# schematic.net
KiCad netlist of a schematic drawn in EAGLE
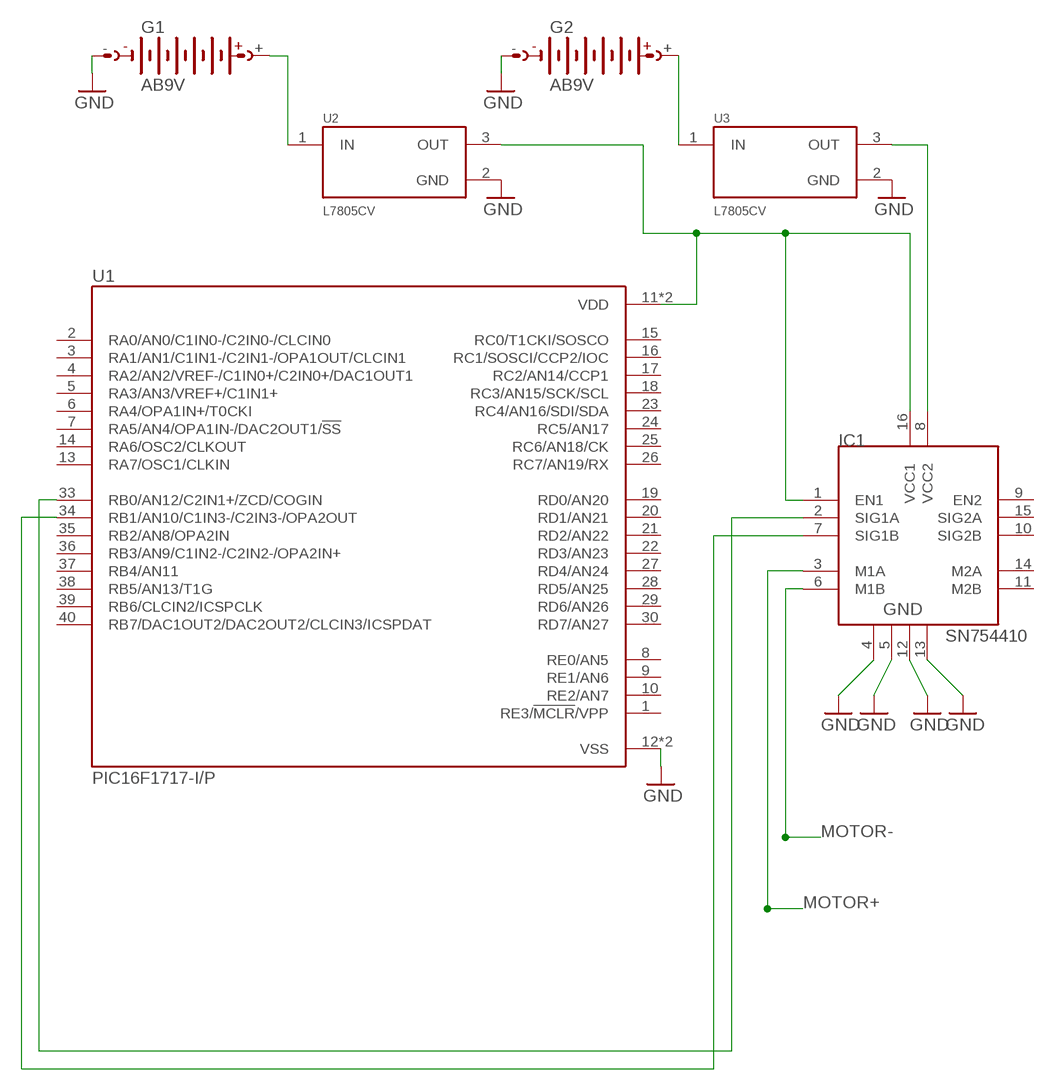
[diagram p0: schematic, sheet 1]

(export (version "E")
  (design (tool "Eeschema 10.0.6"))
  (components
    (comp (ref "G1")
      (value "AB9V")
      (footprint "eagle-import:AB9V")
      (libsource (lib "eagle-import") (part "AB9V"))
    )
    (comp (ref "G2")
      (value "AB9V")
      (footprint "eagle-import:AB9V")
      (libsource (lib "eagle-import") (part "AB9V"))
    )
    (comp (ref "IC1")
      (value "SN754410")
      (footprint "eagle-import:DIP16")
      (libsource (lib "eagle-import") (part "SN754410"))
    )
    (comp (ref "U1")
      (value "PIC16F1717-I/P")
      (footprint "eagle-import:DIP1543W47P254L5321H635Q40")
      (fields (field (name "MF") "Microchip"))
      (libsource (lib "eagle-import") (part "PIC16F1717-I/P"))
    )
    (comp (ref "U2")
      (value "L7805CV")
      (footprint "eagle-import:TO254P460X1020X1945-3P")
      (fields (field (name "MF") "STMicroelectronics"))
      (libsource (lib "eagle-import") (part "L7805CV"))
    )
    (comp (ref "U3")
      (value "L7805CV")
      (footprint "eagle-import:TO254P460X1020X1945-3P")
      (fields (field (name "MF") "STMicroelectronics"))
      (libsource (lib "eagle-import") (part "L7805CV"))
    )
  )
  (nets
    (net (code "1") (name "/MOTOR+") (class "Default")
      (node (ref "IC1") (pin "3") (pinfunction "M1A_3") (pintype "bidirectional"))
    )
    (net (code "2") (name "/MOTOR-") (class "Default")
      (node (ref "IC1") (pin "6") (pinfunction "M1B_6") (pintype "bidirectional"))
    )
    (net (code "3") (name "GND") (class "Default")
      (node (ref "G1") (pin "-") (pinfunction "-_-") (pintype "passive"))
      (node (ref "G2") (pin "-") (pinfunction "-_-") (pintype "passive"))
      (node (ref "IC1") (pin "12") (pinfunction "P12_12") (pintype "power_in"))
      (node (ref "IC1") (pin "13") (pinfunction "P13_13") (pintype "power_in"))
      (node (ref "IC1") (pin "4") (pinfunction "P4_4") (pintype "power_in"))
      (node (ref "IC1") (pin "5") (pinfunction "P5_5") (pintype "power_in"))
      (node (ref "U1") (pin "12") (pinfunction "VSS_12") (pintype "power_in"))
      (node (ref "U1") (pin "31") (pinfunction "VSS_31") (pintype "power_in"))
      (node (ref "U2") (pin "2") (pinfunction "GND_2") (pintype "power_in"))
      (node (ref "U3") (pin "2") (pinfunction "GND_2") (pintype "power_in"))
    )
    (net (code "4") (name "Net-(IC1-EN1)") (class "Default")
      (node (ref "IC1") (pin "1") (pinfunction "EN1_1") (pintype "bidirectional"))
      (node (ref "IC1") (pin "16") (pinfunction "VCC1_16") (pintype "power_in"))
      (node (ref "U1") (pin "11") (pinfunction "VDD_11") (pintype "power_in"))
      (node (ref "U1") (pin "32") (pinfunction "VDD_32") (pintype "power_in"))
      (node (ref "U2") (pin "3") (pinfunction "OUT_3") (pintype "output"))
    )
    (net (code "5") (name "Net-(IC1-SIG1A)") (class "Default")
      (node (ref "IC1") (pin "2") (pinfunction "SIG1A_2") (pintype "bidirectional"))
      (node (ref "U1") (pin "33") (pinfunction "RB0/AN12/C2IN1+/ZCD/COGIN_33") (pintype "bidirectional"))
    )
    (net (code "6") (name "Net-(IC1-SIG1B)") (class "Default")
      (node (ref "IC1") (pin "7") (pinfunction "SIG1B_7") (pintype "bidirectional"))
      (node (ref "U1") (pin "34") (pinfunction "RB1/AN10/C1IN3-/C2IN3-/OPA2OUT_34") (pintype "bidirectional"))
    )
    (net (code "7") (name "Net-(IC1-VCC2)") (class "Default")
      (node (ref "IC1") (pin "8") (pinfunction "VCC2_8") (pintype "power_in"))
      (node (ref "U3") (pin "3") (pinfunction "OUT_3") (pintype "output"))
    )
    (net (code "8") (name "Net-(U2-IN)") (class "Default")
      (node (ref "G1") (pin "+") (pinfunction "+_+") (pintype "passive"))
      (node (ref "U2") (pin "1") (pinfunction "IN_1") (pintype "input"))
    )
    (net (code "9") (name "Net-(U3-IN)") (class "Default")
      (node (ref "G2") (pin "+") (pinfunction "+_+") (pintype "passive"))
      (node (ref "U3") (pin "1") (pinfunction "IN_1") (pintype "input"))
    )
    (net (code "10") (name "unconnected-(IC1-EN2-Pad9)") (class "Default")
      (node (ref "IC1") (pin "9") (pinfunction "EN2_9") (pintype "bidirectional"))
    )
    (net (code "11") (name "unconnected-(IC1-M2A-Pad14)") (class "Default")
      (node (ref "IC1") (pin "14") (pinfunction "M2A_14") (pintype "bidirectional"))
    )
    (net (code "12") (name "unconnected-(IC1-M2B-Pad11)") (class "Default")
      (node (ref "IC1") (pin "11") (pinfunction "M2B_11") (pintype "bidirectional"))
    )
    (net (code "13") (name "unconnected-(IC1-SIG2A-Pad15)") (class "Default")
      (node (ref "IC1") (pin "15") (pinfunction "SIG2A_15") (pintype "bidirectional"))
    )
    (net (code "14") (name "unconnected-(IC1-SIG2B-Pad10)") (class "Default")
      (node (ref "IC1") (pin "10") (pinfunction "SIG2B_10") (pintype "bidirectional"))
    )
    (net (code "15") (name "unconnected-(U1-RA0{slash}AN0{slash}C1IN0-{slash}C2IN0-{slash}CLCIN0-Pad2)") (class "Default")
      (node (ref "U1") (pin "2") (pinfunction "RA0/AN0/C1IN0-/C2IN0-/CLCIN0_2") (pintype "bidirectional"))
    )
    (net (code "16") (name "unconnected-(U1-RA1{slash}AN1{slash}C1IN1-{slash}C2IN1-{slash}OPA1OUT{slash}CLCIN1-Pad3)") (class "Default")
      (node (ref "U1") (pin "3") (pinfunction "RA1/AN1/C1IN1-/C2IN1-/OPA1OUT/CLCIN1_3") (pintype "bidirectional"))
    )
    (net (code "17") (name "unconnected-(U1-RA2{slash}AN2{slash}VREF-{slash}C1IN0+{slash}C2IN0+{slash}DAC1OUT1-Pad4)") (class "Default")
      (node (ref "U1") (pin "4") (pinfunction "RA2/AN2/VREF-/C1IN0+/C2IN0+/DAC1OUT1_4") (pintype "bidirectional"))
    )
    (net (code "18") (name "unconnected-(U1-RA3{slash}AN3{slash}VREF+{slash}C1IN1+-Pad5)") (class "Default")
      (node (ref "U1") (pin "5") (pinfunction "RA3/AN3/VREF+/C1IN1+_5") (pintype "bidirectional"))
    )
    (net (code "19") (name "unconnected-(U1-RA4{slash}OPA1IN+{slash}T0CKI-Pad6)") (class "Default")
      (node (ref "U1") (pin "6") (pinfunction "RA4/OPA1IN+/T0CKI_6") (pintype "bidirectional"))
    )
    (net (code "20") (name "unconnected-(U1-RA5{slash}AN4{slash}OPA1IN-{slash}DAC2OUT1{slash}~{SS}-Pad7)") (class "Default")
      (node (ref "U1") (pin "7") (pinfunction "RA5/AN4/OPA1IN-/DAC2OUT1/~{SS}_7") (pintype "bidirectional"))
    )
    (net (code "21") (name "unconnected-(U1-RA6{slash}OSC2{slash}CLKOUT-Pad14)") (class "Default")
      (node (ref "U1") (pin "14") (pinfunction "RA6/OSC2/CLKOUT_14") (pintype "bidirectional"))
    )
    (net (code "22") (name "unconnected-(U1-RA7{slash}OSC1{slash}CLKIN-Pad13)") (class "Default")
      (node (ref "U1") (pin "13") (pinfunction "RA7/OSC1/CLKIN_13") (pintype "bidirectional"))
    )
    (net (code "23") (name "unconnected-(U1-RB2{slash}AN8{slash}OPA2IN-Pad35)") (class "Default")
      (node (ref "U1") (pin "35") (pinfunction "RB2/AN8/OPA2IN_35") (pintype "bidirectional"))
    )
    (net (code "24") (name "unconnected-(U1-RB3{slash}AN9{slash}C1IN2-{slash}C2IN2-{slash}OPA2IN+-Pad36)") (class "Default")
      (node (ref "U1") (pin "36") (pinfunction "RB3/AN9/C1IN2-/C2IN2-/OPA2IN+_36") (pintype "bidirectional"))
    )
    (net (code "25") (name "unconnected-(U1-RB4{slash}AN11-Pad37)") (class "Default")
      (node (ref "U1") (pin "37") (pinfunction "RB4/AN11_37") (pintype "bidirectional"))
    )
    (net (code "26") (name "unconnected-(U1-RB5{slash}AN13{slash}T1G-Pad38)") (class "Default")
      (node (ref "U1") (pin "38") (pinfunction "RB5/AN13/T1G_38") (pintype "bidirectional"))
    )
    (net (code "27") (name "unconnected-(U1-RB6{slash}CLCIN2{slash}ICSPCLK-Pad39)") (class "Default")
      (node (ref "U1") (pin "39") (pinfunction "RB6/CLCIN2/ICSPCLK_39") (pintype "bidirectional"))
    )
    (net (code "28") (name "unconnected-(U1-RB7{slash}DAC1OUT2{slash}DAC2OUT2{slash}CLCIN3{slash}ICSPDAT-Pad40)") (class "Default")
      (node (ref "U1") (pin "40") (pinfunction "RB7/DAC1OUT2/DAC2OUT2/CLCIN3/ICSPDAT_40") (pintype "bidirectional"))
    )
    (net (code "29") (name "unconnected-(U1-RC0{slash}T1CKI{slash}SOSCO-Pad15)") (class "Default")
      (node (ref "U1") (pin "15") (pinfunction "RC0/T1CKI/SOSCO_15") (pintype "bidirectional"))
    )
    (net (code "30") (name "unconnected-(U1-RC1{slash}SOSCI{slash}CCP2{slash}IOC-Pad16)") (class "Default")
      (node (ref "U1") (pin "16") (pinfunction "RC1/SOSCI/CCP2/IOC_16") (pintype "bidirectional"))
    )
    (net (code "31") (name "unconnected-(U1-RC2{slash}AN14{slash}CCP1-Pad17)") (class "Default")
      (node (ref "U1") (pin "17") (pinfunction "RC2/AN14/CCP1_17") (pintype "bidirectional"))
    )
    (net (code "32") (name "unconnected-(U1-RC3{slash}AN15{slash}SCK{slash}SCL-Pad18)") (class "Default")
      (node (ref "U1") (pin "18") (pinfunction "RC3/AN15/SCK/SCL_18") (pintype "bidirectional"))
    )
    (net (code "33") (name "unconnected-(U1-RC4{slash}AN16{slash}SDI{slash}SDA-Pad23)") (class "Default")
      (node (ref "U1") (pin "23") (pinfunction "RC4/AN16/SDI/SDA_23") (pintype "bidirectional"))
    )
    (net (code "34") (name "unconnected-(U1-RC5{slash}AN17-Pad24)") (class "Default")
      (node (ref "U1") (pin "24") (pinfunction "RC5/AN17_24") (pintype "bidirectional"))
    )
    (net (code "35") (name "unconnected-(U1-RC6{slash}AN18{slash}CK-Pad25)") (class "Default")
      (node (ref "U1") (pin "25") (pinfunction "RC6/AN18/CK_25") (pintype "bidirectional"))
    )
    (net (code "36") (name "unconnected-(U1-RC7{slash}AN19{slash}RX-Pad26)") (class "Default")
      (node (ref "U1") (pin "26") (pinfunction "RC7/AN19/RX_26") (pintype "bidirectional"))
    )
    (net (code "37") (name "unconnected-(U1-RD0{slash}AN20-Pad19)") (class "Default")
      (node (ref "U1") (pin "19") (pinfunction "RD0/AN20_19") (pintype "bidirectional"))
    )
    (net (code "38") (name "unconnected-(U1-RD1{slash}AN21-Pad20)") (class "Default")
      (node (ref "U1") (pin "20") (pinfunction "RD1/AN21_20") (pintype "bidirectional"))
    )
    (net (code "39") (name "unconnected-(U1-RD2{slash}AN22-Pad21)") (class "Default")
      (node (ref "U1") (pin "21") (pinfunction "RD2/AN22_21") (pintype "bidirectional"))
    )
    (net (code "40") (name "unconnected-(U1-RD3{slash}AN23-Pad22)") (class "Default")
      (node (ref "U1") (pin "22") (pinfunction "RD3/AN23_22") (pintype "bidirectional"))
    )
    (net (code "41") (name "unconnected-(U1-RD4{slash}AN24-Pad27)") (class "Default")
      (node (ref "U1") (pin "27") (pinfunction "RD4/AN24_27") (pintype "bidirectional"))
    )
    (net (code "42") (name "unconnected-(U1-RD5{slash}AN25-Pad28)") (class "Default")
      (node (ref "U1") (pin "28") (pinfunction "RD5/AN25_28") (pintype "bidirectional"))
    )
    (net (code "43") (name "unconnected-(U1-RD6{slash}AN26-Pad29)") (class "Default")
      (node (ref "U1") (pin "29") (pinfunction "RD6/AN26_29") (pintype "bidirectional"))
    )
    (net (code "44") (name "unconnected-(U1-RD7{slash}AN27-Pad30)") (class "Default")
      (node (ref "U1") (pin "30") (pinfunction "RD7/AN27_30") (pintype "bidirectional"))
    )
    (net (code "45") (name "unconnected-(U1-RE0{slash}AN5-Pad8)") (class "Default")
      (node (ref "U1") (pin "8") (pinfunction "RE0/AN5_8") (pintype "bidirectional"))
    )
    (net (code "46") (name "unconnected-(U1-RE1{slash}AN6-Pad9)") (class "Default")
      (node (ref "U1") (pin "9") (pinfunction "RE1/AN6_9") (pintype "bidirectional"))
    )
    (net (code "47") (name "unconnected-(U1-RE2{slash}AN7-Pad10)") (class "Default")
      (node (ref "U1") (pin "10") (pinfunction "RE2/AN7_10") (pintype "bidirectional"))
    )
    (net (code "48") (name "unconnected-(U1-RE3{slash}~{MCLR}{slash}VPP-Pad1)") (class "Default")
      (node (ref "U1") (pin "1") (pinfunction "RE3/~{MCLR}/VPP_1") (pintype "bidirectional"))
    )
  )
)
